# untitled.net
KiCad netlist of a schematic drawn in EAGLE
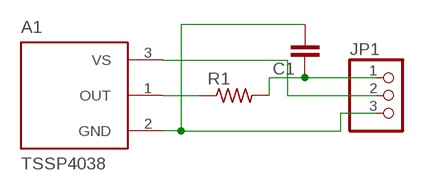
[diagram p0: schematic, sheet 1]

(export (version "E")
  (design (tool "Eeschema 10.0.6"))
  (components
    (comp (ref "A1")
      (value "TSSP4038")
      (footprint "eagle-import:XDCR_TSSP4038")
      (fields (field (name "MF") "Vishay Semiconductor"))
      (libsource (lib "eagle-import") (part "TSSP4038"))
    )
    (comp (ref "C1")
      (value "C-EUC0402")
      (footprint "eagle-import:C0402")
      (libsource (lib "eagle-import") (part "C-EUC0402"))
    )
    (comp (ref "JP1")
      (value "PINHD-1X3/90")
      (footprint "eagle-import:1X03_90")
      (libsource (lib "eagle-import") (part "PINHD-1X3/90"))
    )
    (comp (ref "R1")
      (value "R-US_R0402")
      (footprint "eagle-import:R0402")
      (libsource (lib "eagle-import") (part "R-US_R0402"))
    )
  )
  (nets
    (net (code "1") (name "Net-(A1-GND)") (class "Default")
      (node (ref "A1") (pin "2") (pinfunction "GND_2") (pintype "power_in"))
      (node (ref "C1") (pin "2") (pinfunction "2_2") (pintype "passive"))
      (node (ref "JP1") (pin "3") (pinfunction "3_3") (pintype "passive"))
    )
    (net (code "2") (name "Net-(A1-OUT)") (class "Default")
      (node (ref "A1") (pin "1") (pinfunction "OUT_1") (pintype "output"))
      (node (ref "R1") (pin "1") (pinfunction "1_1") (pintype "passive"))
    )
    (net (code "3") (name "Net-(A1-VS)") (class "Default")
      (node (ref "A1") (pin "3") (pinfunction "VS_3") (pintype "power_in"))
      (node (ref "JP1") (pin "2") (pinfunction "2_2") (pintype "passive"))
    )
    (net (code "4") (name "Net-(C1-Pad1)") (class "Default")
      (node (ref "C1") (pin "1") (pinfunction "1_1") (pintype "passive"))
      (node (ref "JP1") (pin "1") (pinfunction "1_1") (pintype "passive"))
      (node (ref "R1") (pin "2") (pinfunction "2_2") (pintype "passive"))
    )
  )
)
